# Outputs.net
KiCad netlist of a schematic drawn in Altium Designer
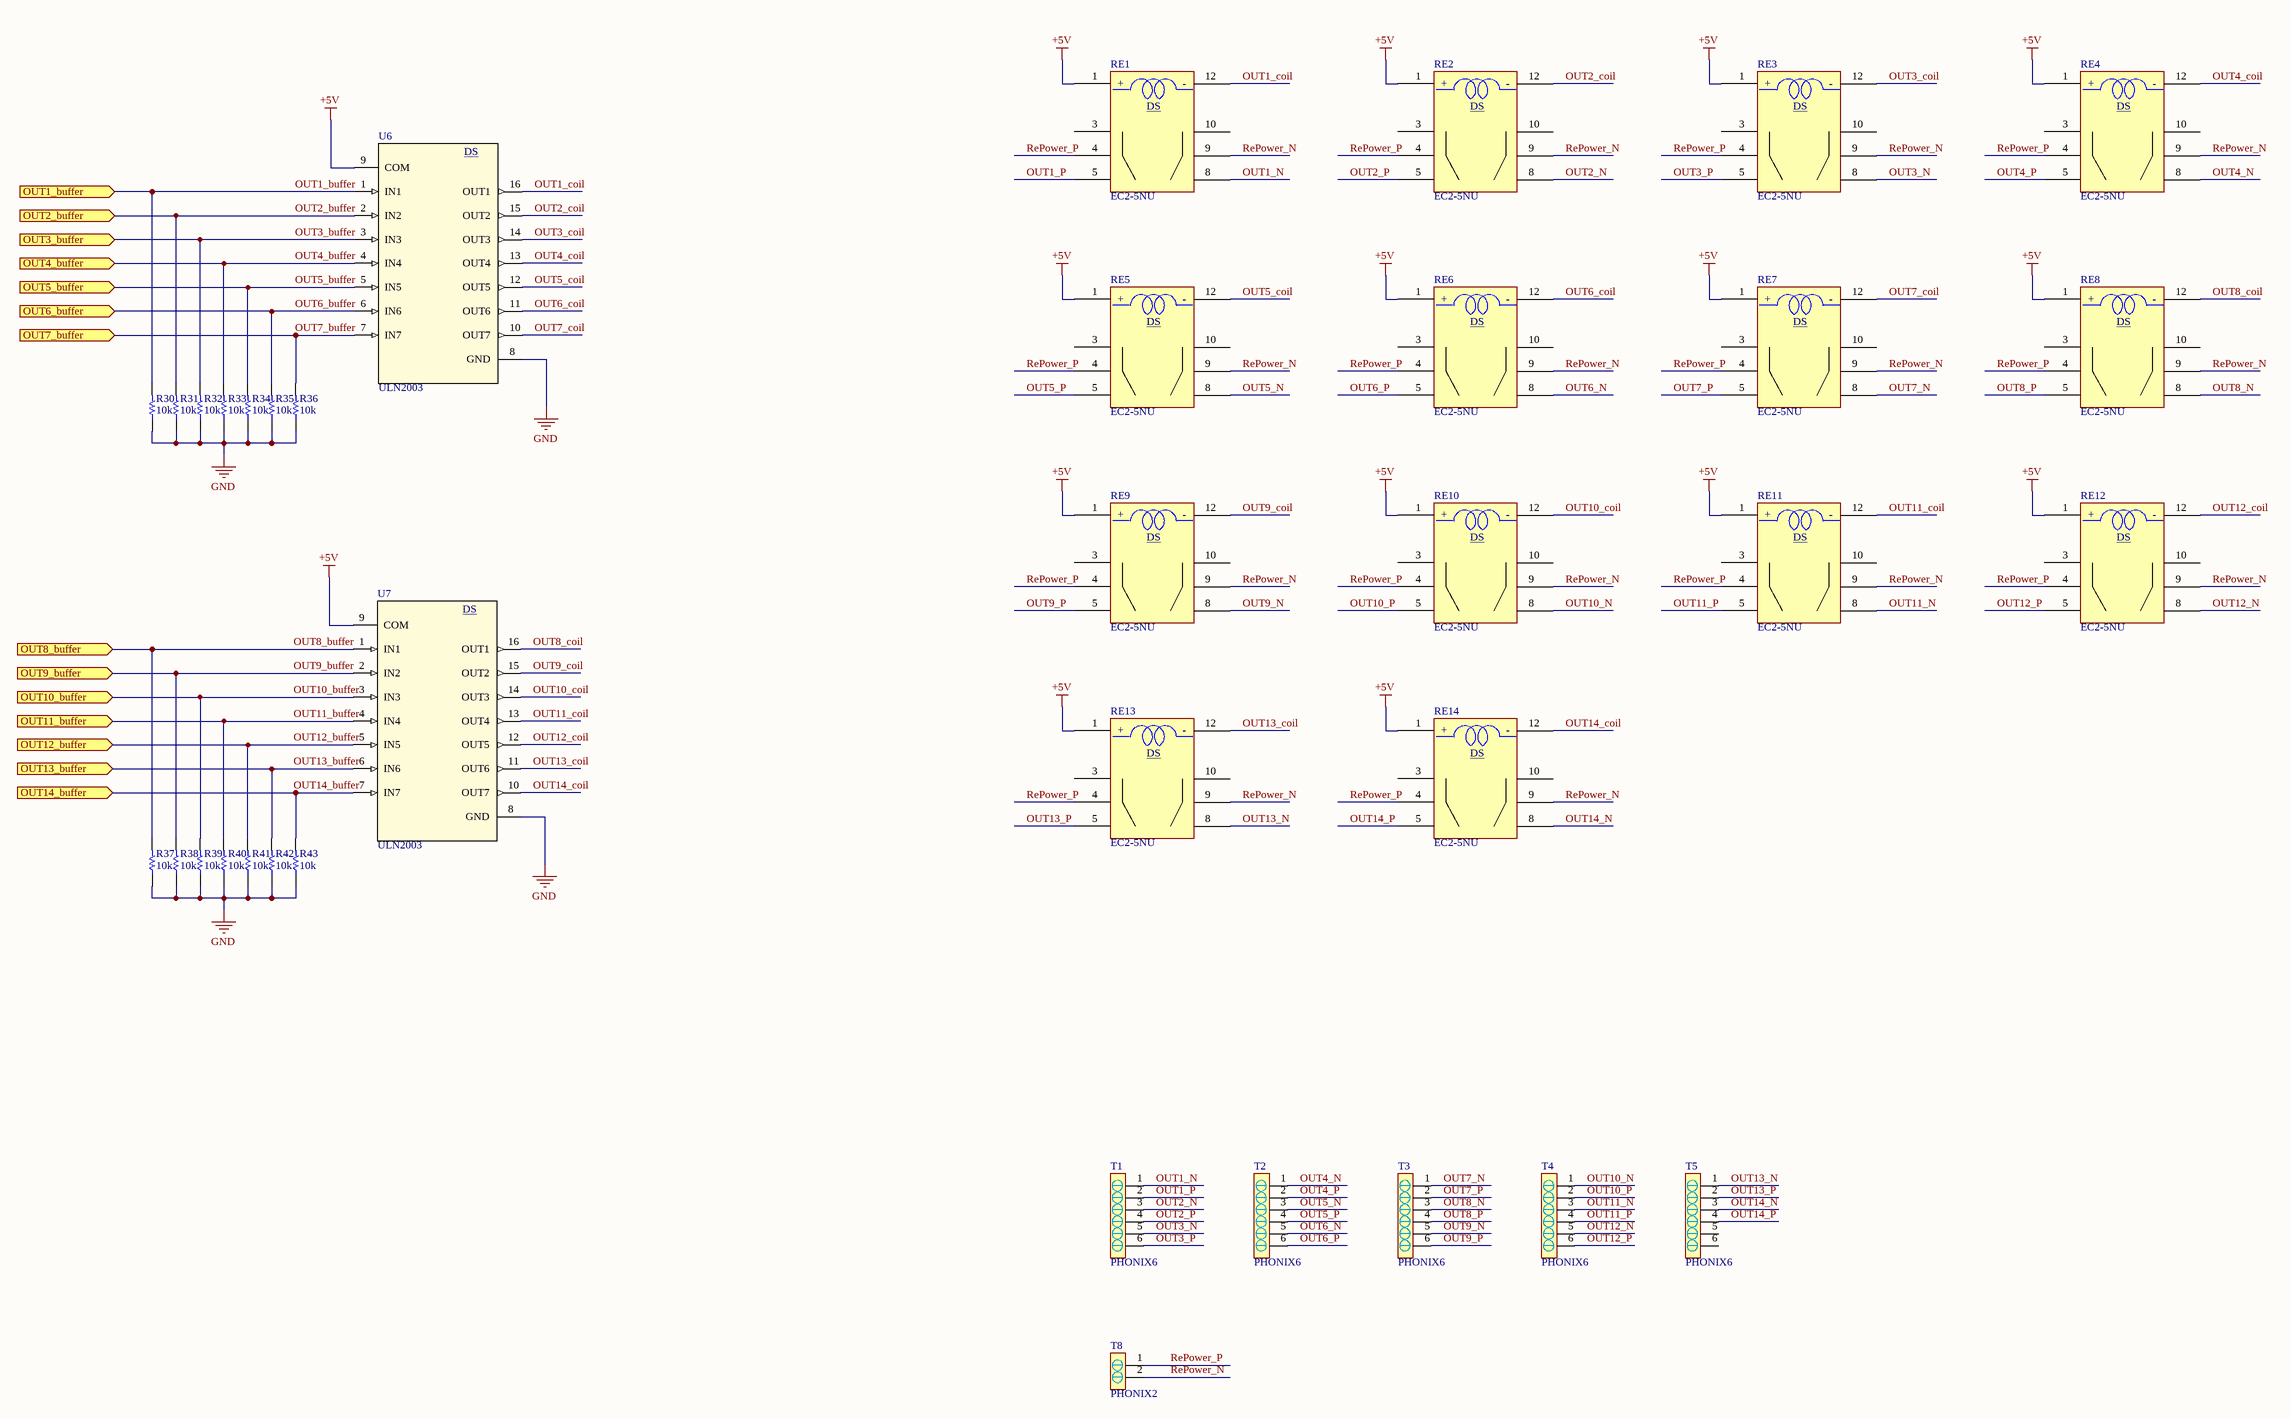
[diagram p0: Outputs.SchDoc]

(export (version "E")
  (design (tool "Eeschema 10.0.6"))
  (components
    (comp (ref "R30")
      (value "10k")
      (footprint "R-805")
      (description "Resistor")
      (fields (field (name "Comment") "R-805"))
      (libsource (lib "AfraLIB") (part "R-805"))
    )
    (comp (ref "R31")
      (value "10k")
      (footprint "R-805")
      (description "Resistor")
      (fields (field (name "Comment") "R-805"))
      (libsource (lib "AfraLIB") (part "R-805"))
    )
    (comp (ref "R32")
      (value "10k")
      (footprint "R-805")
      (description "Resistor")
      (fields (field (name "Comment") "R-805"))
      (libsource (lib "AfraLIB") (part "R-805"))
    )
    (comp (ref "R33")
      (value "10k")
      (footprint "R-805")
      (description "Resistor")
      (fields (field (name "Comment") "R-805"))
      (libsource (lib "AfraLIB") (part "R-805"))
    )
    (comp (ref "R34")
      (value "10k")
      (footprint "R-805")
      (description "Resistor")
      (fields (field (name "Comment") "R-805"))
      (libsource (lib "AfraLIB") (part "R-805"))
    )
    (comp (ref "R35")
      (value "10k")
      (footprint "R-805")
      (description "Resistor")
      (fields (field (name "Comment") "R-805"))
      (libsource (lib "AfraLIB") (part "R-805"))
    )
    (comp (ref "R36")
      (value "10k")
      (footprint "R-805")
      (description "Resistor")
      (fields (field (name "Comment") "R-805"))
      (libsource (lib "AfraLIB") (part "R-805"))
    )
    (comp (ref "R37")
      (value "10k")
      (footprint "R-805")
      (description "Resistor")
      (fields (field (name "Comment") "R-805"))
      (libsource (lib "AfraLIB") (part "R-805"))
    )
    (comp (ref "R38")
      (value "10k")
      (footprint "R-805")
      (description "Resistor")
      (fields (field (name "Comment") "R-805"))
      (libsource (lib "AfraLIB") (part "R-805"))
    )
    (comp (ref "R39")
      (value "10k")
      (footprint "R-805")
      (description "Resistor")
      (fields (field (name "Comment") "R-805"))
      (libsource (lib "AfraLIB") (part "R-805"))
    )
    (comp (ref "R40")
      (value "10k")
      (footprint "R-805")
      (description "Resistor")
      (fields (field (name "Comment") "R-805"))
      (libsource (lib "AfraLIB") (part "R-805"))
    )
    (comp (ref "R41")
      (value "10k")
      (footprint "R-805")
      (description "Resistor")
      (fields (field (name "Comment") "R-805"))
      (libsource (lib "AfraLIB") (part "R-805"))
    )
    (comp (ref "R42")
      (value "10k")
      (footprint "R-805")
      (description "Resistor")
      (fields (field (name "Comment") "R-805"))
      (libsource (lib "AfraLIB") (part "R-805"))
    )
    (comp (ref "R43")
      (value "10k")
      (footprint "R-805")
      (description "Resistor")
      (fields (field (name "Comment") "R-805"))
      (libsource (lib "AfraLIB") (part "R-805"))
    )
    (comp (ref "RE1") (value "EC2-5NU") (footprint "EC2-5NU") (libsource (lib "AfraLIB") (part "EC2_5NU")))
    (comp (ref "RE2") (value "EC2-5NU") (footprint "EC2-5NU") (libsource (lib "AfraLIB") (part "EC2_5NU")))
    (comp (ref "RE3") (value "EC2-5NU") (footprint "EC2-5NU") (libsource (lib "AfraLIB") (part "EC2_5NU")))
    (comp (ref "RE4") (value "EC2-5NU") (footprint "EC2-5NU") (libsource (lib "AfraLIB") (part "EC2_5NU")))
    (comp (ref "RE5") (value "EC2-5NU") (footprint "EC2-5NU") (libsource (lib "AfraLIB") (part "EC2_5NU")))
    (comp (ref "RE6") (value "EC2-5NU") (footprint "EC2-5NU") (libsource (lib "AfraLIB") (part "EC2_5NU")))
    (comp (ref "RE7") (value "EC2-5NU") (footprint "EC2-5NU") (libsource (lib "AfraLIB") (part "EC2_5NU")))
    (comp (ref "RE8") (value "EC2-5NU") (footprint "EC2-5NU") (libsource (lib "AfraLIB") (part "EC2_5NU")))
    (comp (ref "RE9") (value "EC2-5NU") (footprint "EC2-5NU") (libsource (lib "AfraLIB") (part "EC2_5NU")))
    (comp (ref "RE10") (value "EC2-5NU") (footprint "EC2-5NU") (libsource (lib "AfraLIB") (part "EC2_5NU")))
    (comp (ref "RE11") (value "EC2-5NU") (footprint "EC2-5NU") (libsource (lib "AfraLIB") (part "EC2_5NU")))
    (comp (ref "RE12") (value "EC2-5NU") (footprint "EC2-5NU") (libsource (lib "AfraLIB") (part "EC2_5NU")))
    (comp (ref "RE13") (value "EC2-5NU") (footprint "EC2-5NU") (libsource (lib "AfraLIB") (part "EC2_5NU")))
    (comp (ref "RE14") (value "EC2-5NU") (footprint "EC2-5NU") (libsource (lib "AfraLIB") (part "EC2_5NU")))
    (comp (ref "T1") (value "PHONIX6") (footprint "PHONIX6") (libsource (lib "AfraLIB") (part "PHONIX6")))
    (comp (ref "T2") (value "PHONIX6") (footprint "PHONIX6") (libsource (lib "AfraLIB") (part "PHONIX6")))
    (comp (ref "T3") (value "PHONIX6") (footprint "PHONIX6") (libsource (lib "AfraLIB") (part "PHONIX6")))
    (comp (ref "T4") (value "PHONIX6") (footprint "PHONIX6") (libsource (lib "AfraLIB") (part "PHONIX6")))
    (comp (ref "T5") (value "PHONIX6") (footprint "PHONIX6") (libsource (lib "AfraLIB") (part "PHONIX6")))
    (comp (ref "T8") (value "PHONIX2") (footprint "PHONIX2") (libsource (lib "AfraLIB") (part "PHONIX2")))
    (comp (ref "U6")
      (value "ULN2003")
      (footprint "ULN20003")
      (description "No Description Available")
      (fields
        (field (name "PARTNUMBER") "ULN2003ADR")
        (field (name "MANUFACTURER") "Texas Instruments")
        (field (name "COPYRIGHT") "Copyright (C) 2018 Accelerated Designs. All rights reserved")
      )
      (libsource (lib "AfraLIB") (part "ULN2003"))
    )
    (comp (ref "U7")
      (value "ULN2003")
      (footprint "ULN20003")
      (description "No Description Available")
      (fields
        (field (name "PARTNUMBER") "ULN2003ADR")
        (field (name "MANUFACTURER") "Texas Instruments")
        (field (name "COPYRIGHT") "Copyright (C) 2018 Accelerated Designs. All rights reserved")
      )
      (libsource (lib "AfraLIB") (part "ULN2003"))
    )
  )
  (nets
    (net (code "1") (name "+5V") (class "Default")
      (node (ref "RE1") (pin "1") (pinfunction "1_1") (pintype "passive"))
      (node (ref "RE10") (pin "1") (pinfunction "1_1") (pintype "passive"))
      (node (ref "RE11") (pin "1") (pinfunction "1_1") (pintype "passive"))
      (node (ref "RE12") (pin "1") (pinfunction "1_1") (pintype "passive"))
      (node (ref "RE13") (pin "1") (pinfunction "1_1") (pintype "passive"))
      (node (ref "RE14") (pin "1") (pinfunction "1_1") (pintype "passive"))
      (node (ref "RE2") (pin "1") (pinfunction "1_1") (pintype "passive"))
      (node (ref "RE3") (pin "1") (pinfunction "1_1") (pintype "passive"))
      (node (ref "RE4") (pin "1") (pinfunction "1_1") (pintype "passive"))
      (node (ref "RE5") (pin "1") (pinfunction "1_1") (pintype "passive"))
      (node (ref "RE6") (pin "1") (pinfunction "1_1") (pintype "passive"))
      (node (ref "RE7") (pin "1") (pinfunction "1_1") (pintype "passive"))
      (node (ref "RE8") (pin "1") (pinfunction "1_1") (pintype "passive"))
      (node (ref "RE9") (pin "1") (pinfunction "1_1") (pintype "passive"))
      (node (ref "U6") (pin "9") (pinfunction "COM_9") (pintype "power_in"))
      (node (ref "U7") (pin "9") (pinfunction "COM_9") (pintype "power_in"))
    )
    (net (code "2") (name "/OUT1_N") (class "Default")
      (node (ref "RE1") (pin "8") (pinfunction "8_8") (pintype "passive"))
      (node (ref "T1") (pin "1") (pintype "passive"))
    )
    (net (code "3") (name "/OUT1_P") (class "Default")
      (node (ref "RE1") (pin "5") (pinfunction "5_5") (pintype "passive"))
      (node (ref "T1") (pin "2") (pintype "passive"))
    )
    (net (code "4") (name "/OUT1_buffer") (class "Default")
      (node (ref "R30") (pin "2") (pinfunction "2_2") (pintype "passive"))
      (node (ref "U6") (pin "1") (pinfunction "IN1_1") (pintype "input"))
    )
    (net (code "5") (name "/OUT1_coil") (class "Default")
      (node (ref "RE1") (pin "12") (pinfunction "12_12") (pintype "passive"))
      (node (ref "U6") (pin "16") (pinfunction "OUT1_16") (pintype "output"))
    )
    (net (code "6") (name "/OUT2_N") (class "Default")
      (node (ref "RE2") (pin "8") (pinfunction "8_8") (pintype "passive"))
      (node (ref "T1") (pin "3") (pintype "passive"))
    )
    (net (code "7") (name "/OUT2_P") (class "Default")
      (node (ref "RE2") (pin "5") (pinfunction "5_5") (pintype "passive"))
      (node (ref "T1") (pin "4") (pintype "passive"))
    )
    (net (code "8") (name "/OUT2_buffer") (class "Default")
      (node (ref "R31") (pin "2") (pinfunction "2_2") (pintype "passive"))
      (node (ref "U6") (pin "2") (pinfunction "IN2_2") (pintype "input"))
    )
    (net (code "9") (name "/OUT2_coil") (class "Default")
      (node (ref "RE2") (pin "12") (pinfunction "12_12") (pintype "passive"))
      (node (ref "U6") (pin "15") (pinfunction "OUT2_15") (pintype "output"))
    )
    (net (code "10") (name "/OUT3_N") (class "Default")
      (node (ref "RE3") (pin "8") (pinfunction "8_8") (pintype "passive"))
      (node (ref "T1") (pin "5") (pintype "passive"))
    )
    (net (code "11") (name "/OUT3_P") (class "Default")
      (node (ref "RE3") (pin "5") (pinfunction "5_5") (pintype "passive"))
      (node (ref "T1") (pin "6") (pintype "passive"))
    )
    (net (code "12") (name "/OUT3_buffer") (class "Default")
      (node (ref "R32") (pin "2") (pinfunction "2_2") (pintype "passive"))
      (node (ref "U6") (pin "3") (pinfunction "IN3_3") (pintype "input"))
    )
    (net (code "13") (name "/OUT3_coil") (class "Default")
      (node (ref "RE3") (pin "12") (pinfunction "12_12") (pintype "passive"))
      (node (ref "U6") (pin "14") (pinfunction "OUT3_14") (pintype "output"))
    )
    (net (code "14") (name "/OUT4_N") (class "Default")
      (node (ref "RE4") (pin "8") (pinfunction "8_8") (pintype "passive"))
      (node (ref "T2") (pin "1") (pintype "passive"))
    )
    (net (code "15") (name "/OUT4_P") (class "Default")
      (node (ref "RE4") (pin "5") (pinfunction "5_5") (pintype "passive"))
      (node (ref "T2") (pin "2") (pintype "passive"))
    )
    (net (code "16") (name "/OUT4_buffer") (class "Default")
      (node (ref "R33") (pin "2") (pinfunction "2_2") (pintype "passive"))
      (node (ref "U6") (pin "4") (pinfunction "IN4_4") (pintype "input"))
    )
    (net (code "17") (name "/OUT4_coil") (class "Default")
      (node (ref "RE4") (pin "12") (pinfunction "12_12") (pintype "passive"))
      (node (ref "U6") (pin "13") (pinfunction "OUT4_13") (pintype "output"))
    )
    (net (code "18") (name "/OUT5_N") (class "Default")
      (node (ref "RE5") (pin "8") (pinfunction "8_8") (pintype "passive"))
      (node (ref "T2") (pin "3") (pintype "passive"))
    )
    (net (code "19") (name "/OUT5_P") (class "Default")
      (node (ref "RE5") (pin "5") (pinfunction "5_5") (pintype "passive"))
      (node (ref "T2") (pin "4") (pintype "passive"))
    )
    (net (code "20") (name "/OUT5_buffer") (class "Default")
      (node (ref "R34") (pin "2") (pinfunction "2_2") (pintype "passive"))
      (node (ref "U6") (pin "5") (pinfunction "IN5_5") (pintype "input"))
    )
    (net (code "21") (name "/OUT5_coil") (class "Default")
      (node (ref "RE5") (pin "12") (pinfunction "12_12") (pintype "passive"))
      (node (ref "U6") (pin "12") (pinfunction "OUT5_12") (pintype "output"))
    )
    (net (code "22") (name "/OUT6_N") (class "Default")
      (node (ref "RE6") (pin "8") (pinfunction "8_8") (pintype "passive"))
      (node (ref "T2") (pin "5") (pintype "passive"))
    )
    (net (code "23") (name "/OUT6_P") (class "Default")
      (node (ref "RE6") (pin "5") (pinfunction "5_5") (pintype "passive"))
      (node (ref "T2") (pin "6") (pintype "passive"))
    )
    (net (code "24") (name "/OUT6_buffer") (class "Default")
      (node (ref "R35") (pin "2") (pinfunction "2_2") (pintype "passive"))
      (node (ref "U6") (pin "6") (pinfunction "IN6_6") (pintype "input"))
    )
    (net (code "25") (name "/OUT6_coil") (class "Default")
      (node (ref "RE6") (pin "12") (pinfunction "12_12") (pintype "passive"))
      (node (ref "U6") (pin "11") (pinfunction "OUT6_11") (pintype "output"))
    )
    (net (code "26") (name "/OUT7_N") (class "Default")
      (node (ref "RE7") (pin "8") (pinfunction "8_8") (pintype "passive"))
      (node (ref "T3") (pin "1") (pintype "passive"))
    )
    (net (code "27") (name "/OUT7_P") (class "Default")
      (node (ref "RE7") (pin "5") (pinfunction "5_5") (pintype "passive"))
      (node (ref "T3") (pin "2") (pintype "passive"))
    )
    (net (code "28") (name "/OUT7_buffer") (class "Default")
      (node (ref "R36") (pin "2") (pinfunction "2_2") (pintype "passive"))
      (node (ref "U6") (pin "7") (pinfunction "IN7_7") (pintype "input"))
    )
    (net (code "29") (name "/OUT7_coil") (class "Default")
      (node (ref "RE7") (pin "12") (pinfunction "12_12") (pintype "passive"))
      (node (ref "U6") (pin "10") (pinfunction "OUT7_10") (pintype "output"))
    )
    (net (code "30") (name "/OUT8_N") (class "Default")
      (node (ref "RE8") (pin "8") (pinfunction "8_8") (pintype "passive"))
      (node (ref "T3") (pin "3") (pintype "passive"))
    )
    (net (code "31") (name "/OUT8_P") (class "Default")
      (node (ref "RE8") (pin "5") (pinfunction "5_5") (pintype "passive"))
      (node (ref "T3") (pin "4") (pintype "passive"))
    )
    (net (code "32") (name "/OUT8_buffer") (class "Default")
      (node (ref "R37") (pin "2") (pinfunction "2_2") (pintype "passive"))
      (node (ref "U7") (pin "1") (pinfunction "IN1_1") (pintype "input"))
    )
    (net (code "33") (name "/OUT8_coil") (class "Default")
      (node (ref "RE8") (pin "12") (pinfunction "12_12") (pintype "passive"))
      (node (ref "U7") (pin "16") (pinfunction "OUT1_16") (pintype "output"))
    )
    (net (code "34") (name "/OUT9_N") (class "Default")
      (node (ref "RE9") (pin "8") (pinfunction "8_8") (pintype "passive"))
      (node (ref "T3") (pin "5") (pintype "passive"))
    )
    (net (code "35") (name "/OUT9_P") (class "Default")
      (node (ref "RE9") (pin "5") (pinfunction "5_5") (pintype "passive"))
      (node (ref "T3") (pin "6") (pintype "passive"))
    )
    (net (code "36") (name "/OUT9_buffer") (class "Default")
      (node (ref "R38") (pin "2") (pinfunction "2_2") (pintype "passive"))
      (node (ref "U7") (pin "2") (pinfunction "IN2_2") (pintype "input"))
    )
    (net (code "37") (name "/OUT9_coil") (class "Default")
      (node (ref "RE9") (pin "12") (pinfunction "12_12") (pintype "passive"))
      (node (ref "U7") (pin "15") (pinfunction "OUT2_15") (pintype "output"))
    )
    (net (code "38") (name "/OUT10_N") (class "Default")
      (node (ref "RE10") (pin "8") (pinfunction "8_8") (pintype "passive"))
      (node (ref "T4") (pin "1") (pintype "passive"))
    )
    (net (code "39") (name "/OUT10_P") (class "Default")
      (node (ref "RE10") (pin "5") (pinfunction "5_5") (pintype "passive"))
      (node (ref "T4") (pin "2") (pintype "passive"))
    )
    (net (code "40") (name "/OUT10_buffer") (class "Default")
      (node (ref "R39") (pin "2") (pinfunction "2_2") (pintype "passive"))
      (node (ref "U7") (pin "3") (pinfunction "IN3_3") (pintype "input"))
    )
    (net (code "41") (name "/OUT10_coil") (class "Default")
      (node (ref "RE10") (pin "12") (pinfunction "12_12") (pintype "passive"))
      (node (ref "U7") (pin "14") (pinfunction "OUT3_14") (pintype "output"))
    )
    (net (code "42") (name "/OUT11_N") (class "Default")
      (node (ref "RE11") (pin "8") (pinfunction "8_8") (pintype "passive"))
      (node (ref "T4") (pin "3") (pintype "passive"))
    )
    (net (code "43") (name "/OUT11_P") (class "Default")
      (node (ref "RE11") (pin "5") (pinfunction "5_5") (pintype "passive"))
      (node (ref "T4") (pin "4") (pintype "passive"))
    )
    (net (code "44") (name "/OUT11_buffer") (class "Default")
      (node (ref "R40") (pin "2") (pinfunction "2_2") (pintype "passive"))
      (node (ref "U7") (pin "4") (pinfunction "IN4_4") (pintype "input"))
    )
    (net (code "45") (name "/OUT11_coil") (class "Default")
      (node (ref "RE11") (pin "12") (pinfunction "12_12") (pintype "passive"))
      (node (ref "U7") (pin "13") (pinfunction "OUT4_13") (pintype "output"))
    )
    (net (code "46") (name "/OUT12_N") (class "Default")
      (node (ref "RE12") (pin "8") (pinfunction "8_8") (pintype "passive"))
      (node (ref "T4") (pin "5") (pintype "passive"))
    )
    (net (code "47") (name "/OUT12_P") (class "Default")
      (node (ref "RE12") (pin "5") (pinfunction "5_5") (pintype "passive"))
      (node (ref "T4") (pin "6") (pintype "passive"))
    )
    (net (code "48") (name "/OUT12_buffer") (class "Default")
      (node (ref "R41") (pin "2") (pinfunction "2_2") (pintype "passive"))
      (node (ref "U7") (pin "5") (pinfunction "IN5_5") (pintype "input"))
    )
    (net (code "49") (name "/OUT12_coil") (class "Default")
      (node (ref "RE12") (pin "12") (pinfunction "12_12") (pintype "passive"))
      (node (ref "U7") (pin "12") (pinfunction "OUT5_12") (pintype "output"))
    )
    (net (code "50") (name "/OUT13_N") (class "Default")
      (node (ref "RE13") (pin "8") (pinfunction "8_8") (pintype "passive"))
      (node (ref "T5") (pin "1") (pintype "passive"))
    )
    (net (code "51") (name "/OUT13_P") (class "Default")
      (node (ref "RE13") (pin "5") (pinfunction "5_5") (pintype "passive"))
      (node (ref "T5") (pin "2") (pintype "passive"))
    )
    (net (code "52") (name "/OUT13_buffer") (class "Default")
      (node (ref "R42") (pin "2") (pinfunction "2_2") (pintype "passive"))
      (node (ref "U7") (pin "6") (pinfunction "IN6_6") (pintype "input"))
    )
    (net (code "53") (name "/OUT13_coil") (class "Default")
      (node (ref "RE13") (pin "12") (pinfunction "12_12") (pintype "passive"))
      (node (ref "U7") (pin "11") (pinfunction "OUT6_11") (pintype "output"))
    )
    (net (code "54") (name "/OUT14_N") (class "Default")
      (node (ref "RE14") (pin "8") (pinfunction "8_8") (pintype "passive"))
      (node (ref "T5") (pin "3") (pintype "passive"))
    )
    (net (code "55") (name "/OUT14_P") (class "Default")
      (node (ref "RE14") (pin "5") (pinfunction "5_5") (pintype "passive"))
      (node (ref "T5") (pin "4") (pintype "passive"))
    )
    (net (code "56") (name "/OUT14_buffer") (class "Default")
      (node (ref "R43") (pin "2") (pinfunction "2_2") (pintype "passive"))
      (node (ref "U7") (pin "7") (pinfunction "IN7_7") (pintype "input"))
    )
    (net (code "57") (name "/OUT14_coil") (class "Default")
      (node (ref "RE14") (pin "12") (pinfunction "12_12") (pintype "passive"))
      (node (ref "U7") (pin "10") (pinfunction "OUT7_10") (pintype "output"))
    )
    (net (code "58") (name "/RePower_N") (class "Default")
      (node (ref "RE1") (pin "9") (pinfunction "9_9") (pintype "passive"))
      (node (ref "RE10") (pin "9") (pinfunction "9_9") (pintype "passive"))
      (node (ref "RE11") (pin "9") (pinfunction "9_9") (pintype "passive"))
      (node (ref "RE12") (pin "9") (pinfunction "9_9") (pintype "passive"))
      (node (ref "RE13") (pin "9") (pinfunction "9_9") (pintype "passive"))
      (node (ref "RE14") (pin "9") (pinfunction "9_9") (pintype "passive"))
      (node (ref "RE2") (pin "9") (pinfunction "9_9") (pintype "passive"))
      (node (ref "RE3") (pin "9") (pinfunction "9_9") (pintype "passive"))
      (node (ref "RE4") (pin "9") (pinfunction "9_9") (pintype "passive"))
      (node (ref "RE5") (pin "9") (pinfunction "9_9") (pintype "passive"))
      (node (ref "RE6") (pin "9") (pinfunction "9_9") (pintype "passive"))
      (node (ref "RE7") (pin "9") (pinfunction "9_9") (pintype "passive"))
      (node (ref "RE8") (pin "9") (pinfunction "9_9") (pintype "passive"))
      (node (ref "RE9") (pin "9") (pinfunction "9_9") (pintype "passive"))
      (node (ref "T8") (pin "2") (pintype "passive"))
    )
    (net (code "59") (name "/RePower_P") (class "Default")
      (node (ref "RE1") (pin "4") (pinfunction "4_4") (pintype "passive"))
      (node (ref "RE10") (pin "4") (pinfunction "4_4") (pintype "passive"))
      (node (ref "RE11") (pin "4") (pinfunction "4_4") (pintype "passive"))
      (node (ref "RE12") (pin "4") (pinfunction "4_4") (pintype "passive"))
      (node (ref "RE13") (pin "4") (pinfunction "4_4") (pintype "passive"))
      (node (ref "RE14") (pin "4") (pinfunction "4_4") (pintype "passive"))
      (node (ref "RE2") (pin "4") (pinfunction "4_4") (pintype "passive"))
      (node (ref "RE3") (pin "4") (pinfunction "4_4") (pintype "passive"))
      (node (ref "RE4") (pin "4") (pinfunction "4_4") (pintype "passive"))
      (node (ref "RE5") (pin "4") (pinfunction "4_4") (pintype "passive"))
      (node (ref "RE6") (pin "4") (pinfunction "4_4") (pintype "passive"))
      (node (ref "RE7") (pin "4") (pinfunction "4_4") (pintype "passive"))
      (node (ref "RE8") (pin "4") (pinfunction "4_4") (pintype "passive"))
      (node (ref "RE9") (pin "4") (pinfunction "4_4") (pintype "passive"))
      (node (ref "T8") (pin "1") (pintype "passive"))
    )
    (net (code "60") (name "GND") (class "Default")
      (node (ref "R30") (pin "1") (pinfunction "1_1") (pintype "passive"))
      (node (ref "R31") (pin "1") (pinfunction "1_1") (pintype "passive"))
      (node (ref "R32") (pin "1") (pinfunction "1_1") (pintype "passive"))
      (node (ref "R33") (pin "1") (pinfunction "1_1") (pintype "passive"))
      (node (ref "R34") (pin "1") (pinfunction "1_1") (pintype "passive"))
      (node (ref "R35") (pin "1") (pinfunction "1_1") (pintype "passive"))
      (node (ref "R36") (pin "1") (pinfunction "1_1") (pintype "passive"))
      (node (ref "R37") (pin "1") (pinfunction "1_1") (pintype "passive"))
      (node (ref "R38") (pin "1") (pinfunction "1_1") (pintype "passive"))
      (node (ref "R39") (pin "1") (pinfunction "1_1") (pintype "passive"))
      (node (ref "R40") (pin "1") (pinfunction "1_1") (pintype "passive"))
      (node (ref "R41") (pin "1") (pinfunction "1_1") (pintype "passive"))
      (node (ref "R42") (pin "1") (pinfunction "1_1") (pintype "passive"))
      (node (ref "R43") (pin "1") (pinfunction "1_1") (pintype "passive"))
      (node (ref "U6") (pin "8") (pinfunction "GND_8") (pintype "power_in"))
      (node (ref "U7") (pin "8") (pinfunction "GND_8") (pintype "power_in"))
    )
    (net (code "61") (name "unconnected-(RE1-Pad3)") (class "Default")
      (node (ref "RE1") (pin "3") (pinfunction "3_3") (pintype "passive"))
    )
    (net (code "62") (name "unconnected-(RE1-Pad10)") (class "Default")
      (node (ref "RE1") (pin "10") (pinfunction "10_10") (pintype "passive"))
    )
    (net (code "63") (name "unconnected-(RE2-Pad3)") (class "Default")
      (node (ref "RE2") (pin "3") (pinfunction "3_3") (pintype "passive"))
    )
    (net (code "64") (name "unconnected-(RE2-Pad10)") (class "Default")
      (node (ref "RE2") (pin "10") (pinfunction "10_10") (pintype "passive"))
    )
    (net (code "65") (name "unconnected-(RE3-Pad3)") (class "Default")
      (node (ref "RE3") (pin "3") (pinfunction "3_3") (pintype "passive"))
    )
    (net (code "66") (name "unconnected-(RE3-Pad10)") (class "Default")
      (node (ref "RE3") (pin "10") (pinfunction "10_10") (pintype "passive"))
    )
    (net (code "67") (name "unconnected-(RE4-Pad3)") (class "Default")
      (node (ref "RE4") (pin "3") (pinfunction "3_3") (pintype "passive"))
    )
    (net (code "68") (name "unconnected-(RE4-Pad10)") (class "Default")
      (node (ref "RE4") (pin "10") (pinfunction "10_10") (pintype "passive"))
    )
    (net (code "69") (name "unconnected-(RE5-Pad3)") (class "Default")
      (node (ref "RE5") (pin "3") (pinfunction "3_3") (pintype "passive"))
    )
    (net (code "70") (name "unconnected-(RE5-Pad10)") (class "Default")
      (node (ref "RE5") (pin "10") (pinfunction "10_10") (pintype "passive"))
    )
    (net (code "71") (name "unconnected-(RE6-Pad3)") (class "Default")
      (node (ref "RE6") (pin "3") (pinfunction "3_3") (pintype "passive"))
    )
    (net (code "72") (name "unconnected-(RE6-Pad10)") (class "Default")
      (node (ref "RE6") (pin "10") (pinfunction "10_10") (pintype "passive"))
    )
    (net (code "73") (name "unconnected-(RE7-Pad3)") (class "Default")
      (node (ref "RE7") (pin "3") (pinfunction "3_3") (pintype "passive"))
    )
    (net (code "74") (name "unconnected-(RE7-Pad10)") (class "Default")
      (node (ref "RE7") (pin "10") (pinfunction "10_10") (pintype "passive"))
    )
    (net (code "75") (name "unconnected-(RE8-Pad3)") (class "Default")
      (node (ref "RE8") (pin "3") (pinfunction "3_3") (pintype "passive"))
    )
    (net (code "76") (name "unconnected-(RE8-Pad10)") (class "Default")
      (node (ref "RE8") (pin "10") (pinfunction "10_10") (pintype "passive"))
    )
    (net (code "77") (name "unconnected-(RE9-Pad3)") (class "Default")
      (node (ref "RE9") (pin "3") (pinfunction "3_3") (pintype "passive"))
    )
    (net (code "78") (name "unconnected-(RE9-Pad10)") (class "Default")
      (node (ref "RE9") (pin "10") (pinfunction "10_10") (pintype "passive"))
    )
    (net (code "79") (name "unconnected-(RE10-Pad3)") (class "Default")
      (node (ref "RE10") (pin "3") (pinfunction "3_3") (pintype "passive"))
    )
    (net (code "80") (name "unconnected-(RE10-Pad10)") (class "Default")
      (node (ref "RE10") (pin "10") (pinfunction "10_10") (pintype "passive"))
    )
    (net (code "81") (name "unconnected-(RE11-Pad3)") (class "Default")
      (node (ref "RE11") (pin "3") (pinfunction "3_3") (pintype "passive"))
    )
    (net (code "82") (name "unconnected-(RE11-Pad10)") (class "Default")
      (node (ref "RE11") (pin "10") (pinfunction "10_10") (pintype "passive"))
    )
    (net (code "83") (name "unconnected-(RE12-Pad3)") (class "Default")
      (node (ref "RE12") (pin "3") (pinfunction "3_3") (pintype "passive"))
    )
    (net (code "84") (name "unconnected-(RE12-Pad10)") (class "Default")
      (node (ref "RE12") (pin "10") (pinfunction "10_10") (pintype "passive"))
    )
    (net (code "85") (name "unconnected-(RE13-Pad3)") (class "Default")
      (node (ref "RE13") (pin "3") (pinfunction "3_3") (pintype "passive"))
    )
    (net (code "86") (name "unconnected-(RE13-Pad10)") (class "Default")
      (node (ref "RE13") (pin "10") (pinfunction "10_10") (pintype "passive"))
    )
    (net (code "87") (name "unconnected-(RE14-Pad3)") (class "Default")
      (node (ref "RE14") (pin "3") (pinfunction "3_3") (pintype "passive"))
    )
    (net (code "88") (name "unconnected-(RE14-Pad10)") (class "Default")
      (node (ref "RE14") (pin "10") (pinfunction "10_10") (pintype "passive"))
    )
    (net (code "89") (name "unconnected-(T5-Pad5)") (class "Default")
      (node (ref "T5") (pin "5") (pintype "passive"))
    )
    (net (code "90") (name "unconnected-(T5-Pad6)") (class "Default")
      (node (ref "T5") (pin "6") (pintype "passive"))
    )
  )
)
